# Indicator_LEDs_RGB.net
KiCad netlist of a schematic drawn in Altium Designer
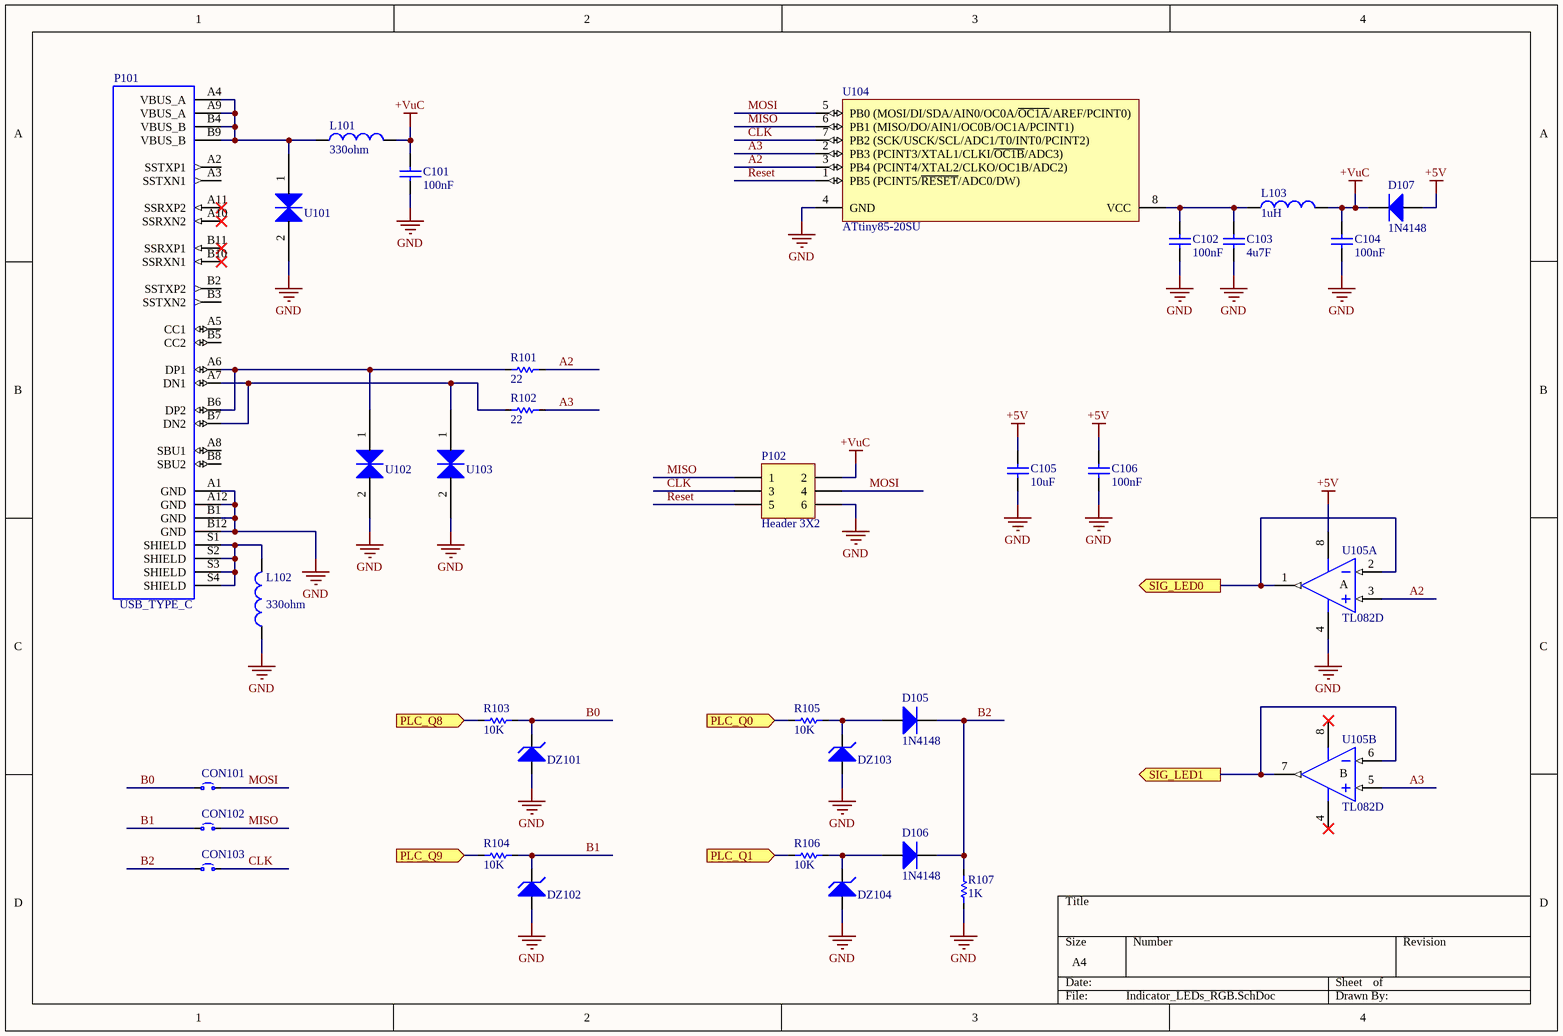
[diagram p0: Indicator_LEDs_RGB.SchDoc]

(export (version "E")
  (design (tool "Eeschema 10.0.6"))
  (components
    (comp (ref "C101")
      (value "Cap Ceramico SMD")
      (footprint "C0603")
      (description "Cap Ceramico SMD 0805")
      (fields (field (name "VALOR") "100nF"))
      (libsource (lib "RUF-Dispositivos-Grales") (part "Cap Ceramico SMD"))
    )
    (comp (ref "C102")
      (value "Cap Ceramico SMD")
      (footprint "C0603")
      (description "Cap Ceramico SMD 0805")
      (fields (field (name "VALOR") "100nF"))
      (libsource (lib "RUF-Dispositivos-Grales") (part "Cap Ceramico SMD"))
    )
    (comp (ref "C103")
      (value "Cap Ceramico SMD")
      (footprint "C0603")
      (description "Cap Ceramico SMD 0805")
      (fields (field (name "VALOR") "4u7F"))
      (libsource (lib "RUF-Dispositivos-Grales") (part "Cap Ceramico SMD"))
    )
    (comp (ref "C104")
      (value "Cap Ceramico SMD")
      (footprint "C0603")
      (description "Cap Ceramico SMD 0805")
      (fields (field (name "VALOR") "100nF"))
      (libsource (lib "RUF-Dispositivos-Grales") (part "Cap Ceramico SMD"))
    )
    (comp (ref "C105")
      (value "Cap Ceramico SMD")
      (footprint "C0603")
      (description "Cap Ceramico SMD 0805")
      (fields (field (name "VALOR") "10uF"))
      (libsource (lib "RUF-Dispositivos-Grales") (part "Cap Ceramico SMD"))
    )
    (comp (ref "C106")
      (value "Cap Ceramico SMD")
      (footprint "C0603")
      (description "Cap Ceramico SMD 0805")
      (fields (field (name "VALOR") "100nF"))
      (libsource (lib "RUF-Dispositivos-Grales") (part "Cap Ceramico SMD"))
    )
    (comp (ref "CON101")
      (value "Puente")
      (footprint "PUENTE 0805")
      (libsource (lib "RUF-Conectores") (part "Puente"))
    )
    (comp (ref "CON102")
      (value "Puente")
      (footprint "PUENTE 0805")
      (libsource (lib "RUF-Conectores") (part "Puente"))
    )
    (comp (ref "CON103")
      (value "Puente")
      (footprint "PUENTE 0805")
      (libsource (lib "RUF-Conectores") (part "Puente"))
    )
    (comp (ref "D105")
      (value "Diodo Rectificador SMD")
      (footprint "SOD-80")
      (description "Diodo Rectificador")
      (fields (field (name "VALOR") "1N4148"))
      (libsource (lib "RUF-Dispositivos-Grales") (part "Diodo Rectificador SMD"))
    )
    (comp (ref "D106")
      (value "Diodo Rectificador SMD")
      (footprint "SOD-80")
      (description "Diodo Rectificador")
      (fields (field (name "VALOR") "1N4148"))
      (libsource (lib "RUF-Dispositivos-Grales") (part "Diodo Rectificador SMD"))
    )
    (comp (ref "D107")
      (value "Diodo Rectificador SMD")
      (footprint "SOD-80")
      (description "Diodo Rectificador")
      (fields (field (name "VALOR") "1N4148"))
      (libsource (lib "RUF-Dispositivos-Grales") (part "Diodo Rectificador SMD"))
    )
    (comp (ref "DZ101")
      (value "Diodo Zenner SMD")
      (footprint "SOD-80")
      (description "Diodo zenner SMD")
      (libsource (lib "RUF-Dispositivos-Grales") (part "Diodo Zenner SMD"))
    )
    (comp (ref "DZ102")
      (value "Diodo Zenner SMD")
      (footprint "SOD-80")
      (description "Diodo zenner SMD")
      (libsource (lib "RUF-Dispositivos-Grales") (part "Diodo Zenner SMD"))
    )
    (comp (ref "DZ103")
      (value "Diodo Zenner SMD")
      (footprint "SOD-80")
      (description "Diodo zenner SMD")
      (libsource (lib "RUF-Dispositivos-Grales") (part "Diodo Zenner SMD"))
    )
    (comp (ref "DZ104")
      (value "Diodo Zenner SMD")
      (footprint "SOD-80")
      (description "Diodo zenner SMD")
      (libsource (lib "RUF-Dispositivos-Grales") (part "Diodo Zenner SMD"))
    )
    (comp (ref "L101")
      (value "330ohm")
      (footprint "J1-0603")
      (description "Inductor")
      (fields (field (name "PUBLISHER") "Altium Limited"))
      (libsource (lib "Miscellaneous Devices") (part "Inductor"))
    )
    (comp (ref "L102")
      (value "330ohm")
      (footprint "J1-0603")
      (description "Inductor")
      (fields (field (name "PUBLISHER") "Altium Limited"))
      (libsource (lib "Miscellaneous Devices") (part "Inductor"))
    )
    (comp (ref "L103")
      (value "1uH")
      (footprint "INDC1608L")
      (description "Inductor")
      (fields (field (name "PUBLISHER") "Altium Limited"))
      (libsource (lib "Miscellaneous Devices") (part "Inductor"))
    )
    (comp (ref "P101")
      (value "USB_TYPE_C")
      (footprint "USB_TYPE_C")
      (fields (field (name "MF") "Amphenol ICC") (field (name "MP") "10137062-00021LF"))
      (libsource (lib "10137062-00021LF") (part "USB Type C"))
    )
    (comp (ref "P102")
      (value "Header 3X2")
      (footprint "HDR2X3")
      (description "Header, 3-Pin, Dual row")
      (fields (field (name "PUBLISHER") "Altium Limited"))
      (libsource (lib "Miscellaneous Connectors") (part "Header 3X2"))
    )
    (comp (ref "R101")
      (value "Res SMD")
      (footprint "R0603")
      (description "Res Smd")
      (fields (field (name "VALOR") "22"))
      (libsource (lib "RUF-Dispositivos-Grales") (part "Res SMD"))
    )
    (comp (ref "R102")
      (value "Res SMD")
      (footprint "R0603")
      (description "Res Smd")
      (fields (field (name "VALOR") "22"))
      (libsource (lib "RUF-Dispositivos-Grales") (part "Res SMD"))
    )
    (comp (ref "R103")
      (value "Res SMD")
      (footprint "R0603")
      (description "Res Smd")
      (fields (field (name "VALOR") "10K"))
      (libsource (lib "RUF-Dispositivos-Grales") (part "Res SMD"))
    )
    (comp (ref "R104")
      (value "Res SMD")
      (footprint "R0603")
      (description "Res Smd")
      (fields (field (name "VALOR") "10K"))
      (libsource (lib "RUF-Dispositivos-Grales") (part "Res SMD"))
    )
    (comp (ref "R105")
      (value "Res SMD")
      (footprint "R0603")
      (description "Res Smd")
      (fields (field (name "VALOR") "10K"))
      (libsource (lib "RUF-Dispositivos-Grales") (part "Res SMD"))
    )
    (comp (ref "R106")
      (value "Res SMD")
      (footprint "R0603")
      (description "Res Smd")
      (fields (field (name "VALOR") "10K"))
      (libsource (lib "RUF-Dispositivos-Grales") (part "Res SMD"))
    )
    (comp (ref "R107")
      (value "Res SMD")
      (footprint "R0603")
      (description "Res Smd")
      (fields (field (name "VALOR") "1K"))
      (libsource (lib "RUF-Dispositivos-Grales") (part "Res SMD"))
    )
    (comp (ref "U101")
      (value "DIODE TVS BIDIR")
      (footprint "J1-0603")
      (libsource (lib "DiodeTVS_Bidir") (part "DIODE TVS BIDIRECTIONAL"))
    )
    (comp (ref "U102")
      (value "DIODE TVS BIDIR")
      (footprint "J1-0603")
      (libsource (lib "DiodeTVS_Bidir") (part "DIODE TVS BIDIRECTIONAL"))
    )
    (comp (ref "U103")
      (value "DIODE TVS BIDIR")
      (footprint "J1-0603")
      (libsource (lib "DiodeTVS_Bidir") (part "DIODE TVS BIDIRECTIONAL"))
    )
    (comp (ref "U104")
      (value "ATtiny85-20SU")
      (footprint "8S2_M")
      (fields (field (name "PUBLISHER") "Altium Limited"))
      (libsource (lib "Atmel Microcontroller 8-Bit tinyAVR") (part "ATtiny85-20SU"))
    )
    (comp (ref "U105")
      (value "TL082D")
      (footprint "D008_L")
      (description "JFET-Input Operational Amplifier")
      (fields (field (name "PUBLISHER") "Altium Limited"))
      (libsource (lib "TI Operational Amplifier") (part "TL082D"))
    )
  )
  (nets
    (net (code "1") (name "+5V") (class "Default")
      (node (ref "C105") (pin "1") (pinfunction "1_1") (pintype "passive"))
      (node (ref "C106") (pin "1") (pinfunction "1_1") (pintype "passive"))
      (node (ref "D107") (pin "1") (pinfunction "A_1") (pintype "passive"))
      (node (ref "U105") (pin "8") (pinfunction "V+_8") (pintype "power_in"))
    )
    (net (code "2") (name "+VuC") (class "Default")
      (node (ref "C101") (pin "1") (pinfunction "1_1") (pintype "passive"))
      (node (ref "C104") (pin "1") (pinfunction "1_1") (pintype "passive"))
      (node (ref "D107") (pin "2") (pinfunction "K_2") (pintype "passive"))
      (node (ref "L101") (pin "2") (pinfunction "2_2") (pintype "passive"))
      (node (ref "L103") (pin "2") (pinfunction "2_2") (pintype "passive"))
      (node (ref "P102") (pin "2") (pinfunction "2_2") (pintype "passive"))
    )
    (net (code "3") (name "/A2") (class "Default")
      (node (ref "R101") (pin "1") (pinfunction "1_1") (pintype "passive"))
      (node (ref "U104") (pin "3") (pinfunction "PB4_(PCINT4/XTAL2/CLKO/OC1B/ADC2)_3") (pintype "bidirectional"))
      (node (ref "U105") (pin "3") (pinfunction "IN+_3") (pintype "input"))
    )
    (net (code "4") (name "/A3") (class "Default")
      (node (ref "R102") (pin "1") (pinfunction "1_1") (pintype "passive"))
      (node (ref "U104") (pin "2") (pinfunction "PB3_(PCINT3/XTAL1/CLKI/~{OC1B}/ADC3)_2") (pintype "bidirectional"))
      (node (ref "U105") (pin "5") (pinfunction "IN+_5") (pintype "input"))
    )
    (net (code "5") (name "/B0") (class "Default")
      (node (ref "CON101") (pin "1") (pinfunction "1_1") (pintype "passive"))
      (node (ref "DZ101") (pin "2") (pinfunction "K_2") (pintype "passive"))
      (node (ref "R103") (pin "2") (pinfunction "2_2") (pintype "passive"))
    )
    (net (code "6") (name "/B1") (class "Default")
      (node (ref "CON102") (pin "1") (pinfunction "1_1") (pintype "passive"))
      (node (ref "DZ102") (pin "2") (pinfunction "K_2") (pintype "passive"))
      (node (ref "R104") (pin "2") (pinfunction "2_2") (pintype "passive"))
    )
    (net (code "7") (name "/B2") (class "Default")
      (node (ref "CON103") (pin "1") (pinfunction "1_1") (pintype "passive"))
      (node (ref "D105") (pin "2") (pinfunction "K_2") (pintype "passive"))
      (node (ref "D106") (pin "2") (pinfunction "K_2") (pintype "passive"))
      (node (ref "R107") (pin "1") (pinfunction "1_1") (pintype "passive"))
    )
    (net (code "8") (name "/CLK") (class "Default")
      (node (ref "CON103") (pin "2") (pinfunction "2_2") (pintype "passive"))
      (node (ref "P102") (pin "3") (pinfunction "3_3") (pintype "passive"))
      (node (ref "U104") (pin "7") (pinfunction "PB2_(SCK/USCK/SCL/ADC1/T0/INT0/PCINT2)_7") (pintype "bidirectional"))
    )
    (net (code "9") (name "/MISO") (class "Default")
      (node (ref "CON102") (pin "2") (pinfunction "2_2") (pintype "passive"))
      (node (ref "P102") (pin "1") (pinfunction "1_1") (pintype "passive"))
      (node (ref "U104") (pin "6") (pinfunction "PB1_(MISO/DO/AIN1/OC0B/OC1A/PCINT1)_6") (pintype "bidirectional"))
    )
    (net (code "10") (name "/MOSI") (class "Default")
      (node (ref "CON101") (pin "2") (pinfunction "2_2") (pintype "passive"))
      (node (ref "P102") (pin "4") (pinfunction "4_4") (pintype "passive"))
      (node (ref "U104") (pin "5") (pinfunction "PB0_(MOSI/DI/SDA/AIN0/OC0A/~{OC1A}/AREF/PCINT0)_5") (pintype "bidirectional"))
    )
    (net (code "11") (name "/PLC_Q0") (class "Default")
      (node (ref "R105") (pin "1") (pinfunction "1_1") (pintype "passive"))
    )
    (net (code "12") (name "/PLC_Q1") (class "Default")
      (node (ref "R106") (pin "1") (pinfunction "1_1") (pintype "passive"))
    )
    (net (code "13") (name "/PLC_Q8") (class "Default")
      (node (ref "R103") (pin "1") (pinfunction "1_1") (pintype "passive"))
    )
    (net (code "14") (name "/PLC_Q9") (class "Default")
      (node (ref "R104") (pin "1") (pinfunction "1_1") (pintype "passive"))
    )
    (net (code "15") (name "/Reset") (class "Default")
      (node (ref "P102") (pin "5") (pinfunction "5_5") (pintype "passive"))
      (node (ref "U104") (pin "1") (pinfunction "PB5_(PCINT5/~{RESET}/ADC0/DW)_1") (pintype "bidirectional"))
    )
    (net (code "16") (name "/SIG_LED0") (class "Default")
      (node (ref "U105") (pin "1") (pinfunction "OUT_1") (pintype "output"))
      (node (ref "U105") (pin "2") (pinfunction "IN-_2") (pintype "input"))
    )
    (net (code "17") (name "/SIG_LED1") (class "Default")
      (node (ref "U105") (pin "6") (pinfunction "IN-_6") (pintype "input"))
      (node (ref "U105") (pin "7") (pinfunction "OUT_7") (pintype "output"))
    )
    (net (code "18") (name "GND") (class "Default")
      (node (ref "C101") (pin "2") (pinfunction "2_2") (pintype "passive"))
      (node (ref "C102") (pin "2") (pinfunction "2_2") (pintype "passive"))
      (node (ref "C103") (pin "1") (pinfunction "1_1") (pintype "passive"))
      (node (ref "C104") (pin "2") (pinfunction "2_2") (pintype "passive"))
      (node (ref "C105") (pin "2") (pinfunction "2_2") (pintype "passive"))
      (node (ref "C106") (pin "2") (pinfunction "2_2") (pintype "passive"))
      (node (ref "DZ101") (pin "1") (pinfunction "A_1") (pintype "passive"))
      (node (ref "DZ102") (pin "1") (pinfunction "A_1") (pintype "passive"))
      (node (ref "DZ103") (pin "1") (pinfunction "A_1") (pintype "passive"))
      (node (ref "DZ104") (pin "1") (pinfunction "A_1") (pintype "passive"))
      (node (ref "L102") (pin "1") (pinfunction "1_1") (pintype "passive"))
      (node (ref "P101") (pin "A1") (pinfunction "GND_A1") (pintype "power_in"))
      (node (ref "P101") (pin "A12") (pinfunction "GND_A12") (pintype "power_in"))
      (node (ref "P101") (pin "B1") (pinfunction "GND_B1") (pintype "power_in"))
      (node (ref "P101") (pin "B12") (pinfunction "GND_B12") (pintype "power_in"))
      (node (ref "P102") (pin "6") (pinfunction "6_6") (pintype "passive"))
      (node (ref "R107") (pin "2") (pinfunction "2_2") (pintype "passive"))
      (node (ref "U101") (pin "2") (pintype "passive"))
      (node (ref "U102") (pin "2") (pintype "passive"))
      (node (ref "U103") (pin "2") (pintype "passive"))
      (node (ref "U104") (pin "4") (pinfunction "GND_4") (pintype "power_in"))
      (node (ref "U105") (pin "4") (pinfunction "V-_4") (pintype "power_in"))
    )
    (net (code "19") (name "Net-(D105-A)") (class "Default")
      (node (ref "D105") (pin "1") (pinfunction "A_1") (pintype "passive"))
      (node (ref "DZ103") (pin "2") (pinfunction "K_2") (pintype "passive"))
      (node (ref "R105") (pin "2") (pinfunction "2_2") (pintype "passive"))
    )
    (net (code "20") (name "Net-(D106-A)") (class "Default")
      (node (ref "D106") (pin "1") (pinfunction "A_1") (pintype "passive"))
      (node (ref "DZ104") (pin "2") (pinfunction "K_2") (pintype "passive"))
      (node (ref "R106") (pin "2") (pinfunction "2_2") (pintype "passive"))
    )
    (net (code "21") (name "Net-(L101-Pad1)") (class "Default")
      (node (ref "L101") (pin "1") (pinfunction "1_1") (pintype "passive"))
      (node (ref "P101") (pin "A4") (pinfunction "VBUS_A_A4") (pintype "power_in"))
      (node (ref "P101") (pin "A9") (pinfunction "VBUS_A_A9") (pintype "power_in"))
      (node (ref "P101") (pin "B4") (pinfunction "VBUS_B_B4") (pintype "power_in"))
      (node (ref "P101") (pin "B9") (pinfunction "VBUS_B_B9") (pintype "power_in"))
      (node (ref "U101") (pin "1") (pintype "passive"))
    )
    (net (code "22") (name "Net-(L102-Pad2)") (class "Default")
      (node (ref "L102") (pin "2") (pinfunction "2_2") (pintype "passive"))
      (node (ref "P101") (pin "S1") (pinfunction "SHIELD_S1") (pintype "power_in"))
      (node (ref "P101") (pin "S2") (pinfunction "SHIELD_S2") (pintype "power_in"))
      (node (ref "P101") (pin "S3") (pinfunction "SHIELD_S3") (pintype "power_in"))
      (node (ref "P101") (pin "S4") (pinfunction "SHIELD_S4") (pintype "power_in"))
    )
    (net (code "23") (name "Net-(P101-DN1)") (class "Default")
      (node (ref "P101") (pin "A7") (pinfunction "DN1_A7") (pintype "bidirectional"))
      (node (ref "P101") (pin "B7") (pinfunction "DN2_B7") (pintype "bidirectional"))
      (node (ref "R102") (pin "2") (pinfunction "2_2") (pintype "passive"))
      (node (ref "U103") (pin "1") (pintype "passive"))
    )
    (net (code "24") (name "Net-(P101-DP1)") (class "Default")
      (node (ref "P101") (pin "A6") (pinfunction "DP1_A6") (pintype "bidirectional"))
      (node (ref "P101") (pin "B6") (pinfunction "DP2_B6") (pintype "bidirectional"))
      (node (ref "R101") (pin "2") (pinfunction "2_2") (pintype "passive"))
      (node (ref "U102") (pin "1") (pintype "passive"))
    )
    (net (code "25") (name "Net-(U104-VCC)") (class "Default")
      (node (ref "C102") (pin "1") (pinfunction "1_1") (pintype "passive"))
      (node (ref "C103") (pin "2") (pinfunction "2_2") (pintype "passive"))
      (node (ref "L103") (pin "1") (pinfunction "1_1") (pintype "passive"))
      (node (ref "U104") (pin "8") (pinfunction "VCC_8") (pintype "power_in"))
    )
    (net (code "26") (name "unconnected-(P101-CC1-PadA5)") (class "Default")
      (node (ref "P101") (pin "A5") (pinfunction "CC1_A5") (pintype "bidirectional"))
    )
    (net (code "27") (name "unconnected-(P101-CC2-PadB5)") (class "Default")
      (node (ref "P101") (pin "B5") (pinfunction "CC2_B5") (pintype "bidirectional"))
    )
    (net (code "28") (name "unconnected-(P101-SBU1-PadA8)") (class "Default")
      (node (ref "P101") (pin "A8") (pinfunction "SBU1_A8") (pintype "bidirectional"))
    )
    (net (code "29") (name "unconnected-(P101-SBU2-PadB8)") (class "Default")
      (node (ref "P101") (pin "B8") (pinfunction "SBU2_B8") (pintype "bidirectional"))
    )
    (net (code "30") (name "unconnected-(P101-SSRXN1-PadB10)") (class "Default")
      (node (ref "P101") (pin "B10") (pinfunction "SSRXN1_B10") (pintype "input+no_connect"))
    )
    (net (code "31") (name "unconnected-(P101-SSRXN2-PadA10)") (class "Default")
      (node (ref "P101") (pin "A10") (pinfunction "SSRXN2_A10") (pintype "input+no_connect"))
    )
    (net (code "32") (name "unconnected-(P101-SSRXP1-PadB11)") (class "Default")
      (node (ref "P101") (pin "B11") (pinfunction "SSRXP1_B11") (pintype "input+no_connect"))
    )
    (net (code "33") (name "unconnected-(P101-SSRXP2-PadA11)") (class "Default")
      (node (ref "P101") (pin "A11") (pinfunction "SSRXP2_A11") (pintype "input+no_connect"))
    )
    (net (code "34") (name "unconnected-(P101-SSTXN1-PadA3)") (class "Default")
      (node (ref "P101") (pin "A3") (pinfunction "SSTXN1_A3") (pintype "output"))
    )
    (net (code "35") (name "unconnected-(P101-SSTXN2-PadB3)") (class "Default")
      (node (ref "P101") (pin "B3") (pinfunction "SSTXN2_B3") (pintype "output"))
    )
    (net (code "36") (name "unconnected-(P101-SSTXP1-PadA2)") (class "Default")
      (node (ref "P101") (pin "A2") (pinfunction "SSTXP1_A2") (pintype "output"))
    )
    (net (code "37") (name "unconnected-(P101-SSTXP2-PadB2)") (class "Default")
      (node (ref "P101") (pin "B2") (pinfunction "SSTXP2_B2") (pintype "output"))
    )
    (net (code "38") (name "unconnected-(U105B-V+-Pad8)") (class "Default")
      (node (ref "U105") (pin "8") (pinfunction "V+_8") (pintype "power_in+no_connect"))
    )
    (net (code "39") (name "unconnected-(U105B-V--Pad4)") (class "Default")
      (node (ref "U105") (pin "4") (pinfunction "V-_4") (pintype "power_in+no_connect"))
    )
  )
)
